# Short_to_VCC_protection.net
KiCad netlist of a schematic drawn in Altium Designer
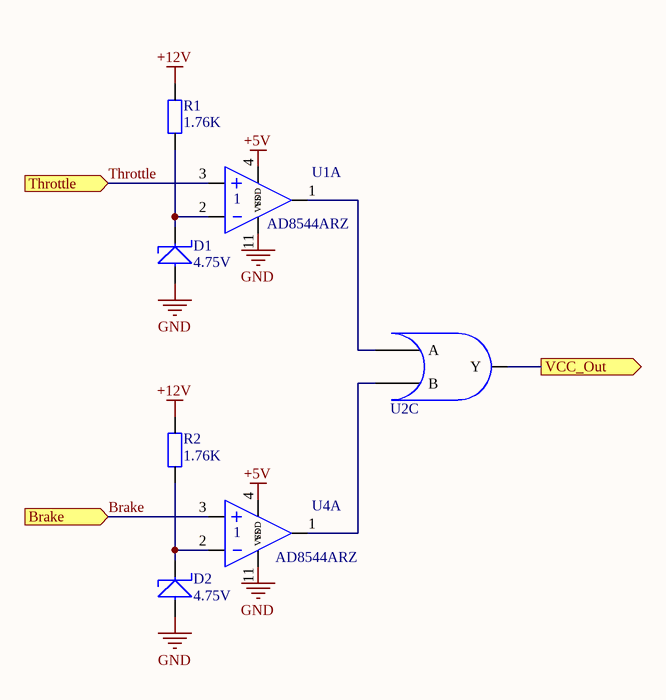
[diagram p0: Short to VCC protection.SchDoc]

(export (version "E")
  (design (tool "Eeschema 10.0.6"))
  (components
    (comp (ref "D1")
      (value "4.75V")
      (footprint "SODFL360X160X130L80X100N")
      (fields
        (field (name "PART NUMBER") "D_4.75V_625mW")
        (field (name "TOLERANCE") "2 %")
        (field (name "MANUFACTURER PART NUMBER") "PDZ4.7BGWX")
      )
      (libsource (lib "FR") (part "Zener_Diode"))
    )
    (comp (ref "D2")
      (value "4.75V")
      (footprint "SODFL360X160X130L80X100N")
      (fields
        (field (name "PART NUMBER") "D_4.75V_625mW")
        (field (name "TOLERANCE") "2 %")
        (field (name "MANUFACTURER PART NUMBER") "PDZ4.7BGWX")
      )
      (libsource (lib "FR") (part "Zener_Diode"))
    )
    (comp (ref "R1")
      (value "1.76K")
      (footprint "RESC160X80X50L30N")
      (fields
        (field (name "PART NUMBER") "R_0603_1.76K_0W1_P")
        (field (name "MANUFACTURER PART NUMBER") "RT0603BRD071K76L")
      )
      (libsource (lib "FR") (part "Resistor"))
    )
    (comp (ref "R2")
      (value "1.76K")
      (footprint "RESC160X80X50L30N")
      (fields
        (field (name "PART NUMBER") "R_0603_1.76K_0W1_P")
        (field (name "MANUFACTURER PART NUMBER") "RT0603BRD071K76L")
      )
      (libsource (lib "FR") (part "Resistor"))
    )
    (comp (ref "U1")
      (value "AD8544ARZ")
      (footprint "SOIC14P127_865X600X175L83X41N")
      (fields
        (field (name "PART NUMBER") "AD8544")
        (field (name "MANUFACTURER PART NUMBER") "AD8544ARZ-REEL")
      )
      (libsource (lib "FR") (part "AD8544"))
    )
    (comp (ref "U2")
      (value "CD4071BM")
      (footprint "SOIC14P127_865X600X175L70X42N")
      (libsource (lib "FR") (part "HEF4071B"))
    )
    (comp (ref "U4")
      (value "AD8544ARZ")
      (footprint "SOIC14P127_865X600X175L83X41N")
      (fields
        (field (name "PART NUMBER") "AD8544")
        (field (name "MANUFACTURER PART NUMBER") "AD8544ARZ-REEL")
      )
      (libsource (lib "FR") (part "AD8544"))
    )
  )
  (nets
    (net (code "1") (name "+5V") (class "Default")
      (node (ref "U1") (pin "4") (pinfunction "VDD_4") (pintype "power_in"))
      (node (ref "U4") (pin "4") (pinfunction "VDD_4") (pintype "power_in"))
    )
    (net (code "2") (name "+12V") (class "Default")
      (node (ref "R1") (pin "1") (pinfunction "1_1") (pintype "passive"))
      (node (ref "R2") (pin "1") (pinfunction "1_1") (pintype "passive"))
    )
    (net (code "3") (name "/Brake") (class "Default") (node (ref "U4") (pin "3") (pintype "passive")))
    (net (code "4") (name "/Throttle") (class "Default") (node (ref "U1") (pin "3") (pintype "passive")))
    (net (code "5") (name "/VCC_Out") (class "Default")
      (node (ref "U2") (pin "10") (pinfunction "Y_10") (pintype "passive"))
    )
    (net (code "6") (name "GND") (class "Default")
      (node (ref "D1") (pin "A") (pinfunction "A_A") (pintype "passive"))
      (node (ref "D2") (pin "A") (pinfunction "A_A") (pintype "passive"))
      (node (ref "U1") (pin "11") (pinfunction "VSS_11") (pintype "power_in"))
      (node (ref "U4") (pin "11") (pinfunction "VSS_11") (pintype "power_in"))
    )
    (net (code "7") (name "Net-(D1-2)") (class "Default")
      (node (ref "D1") (pin "C") (pinfunction "2_C") (pintype "passive"))
      (node (ref "R1") (pin "2") (pinfunction "2_2") (pintype "passive"))
      (node (ref "U1") (pin "2") (pintype "passive"))
    )
    (net (code "8") (name "Net-(D2-2)") (class "Default")
      (node (ref "D2") (pin "C") (pinfunction "2_C") (pintype "passive"))
      (node (ref "R2") (pin "2") (pinfunction "2_2") (pintype "passive"))
      (node (ref "U4") (pin "2") (pintype "passive"))
    )
    (net (code "9") (name "Net-(U2C-A)") (class "Default")
      (node (ref "U1") (pin "1") (pintype "passive"))
      (node (ref "U2") (pin "8") (pinfunction "A_8") (pintype "passive"))
    )
    (net (code "10") (name "Net-(U2C-B)") (class "Default")
      (node (ref "U2") (pin "9") (pinfunction "B_9") (pintype "passive"))
      (node (ref "U4") (pin "1") (pintype "passive"))
    )
  )
)
